# Indicador_de_8_bits.net
KiCad netlist of a schematic drawn in EasyEDA Pro
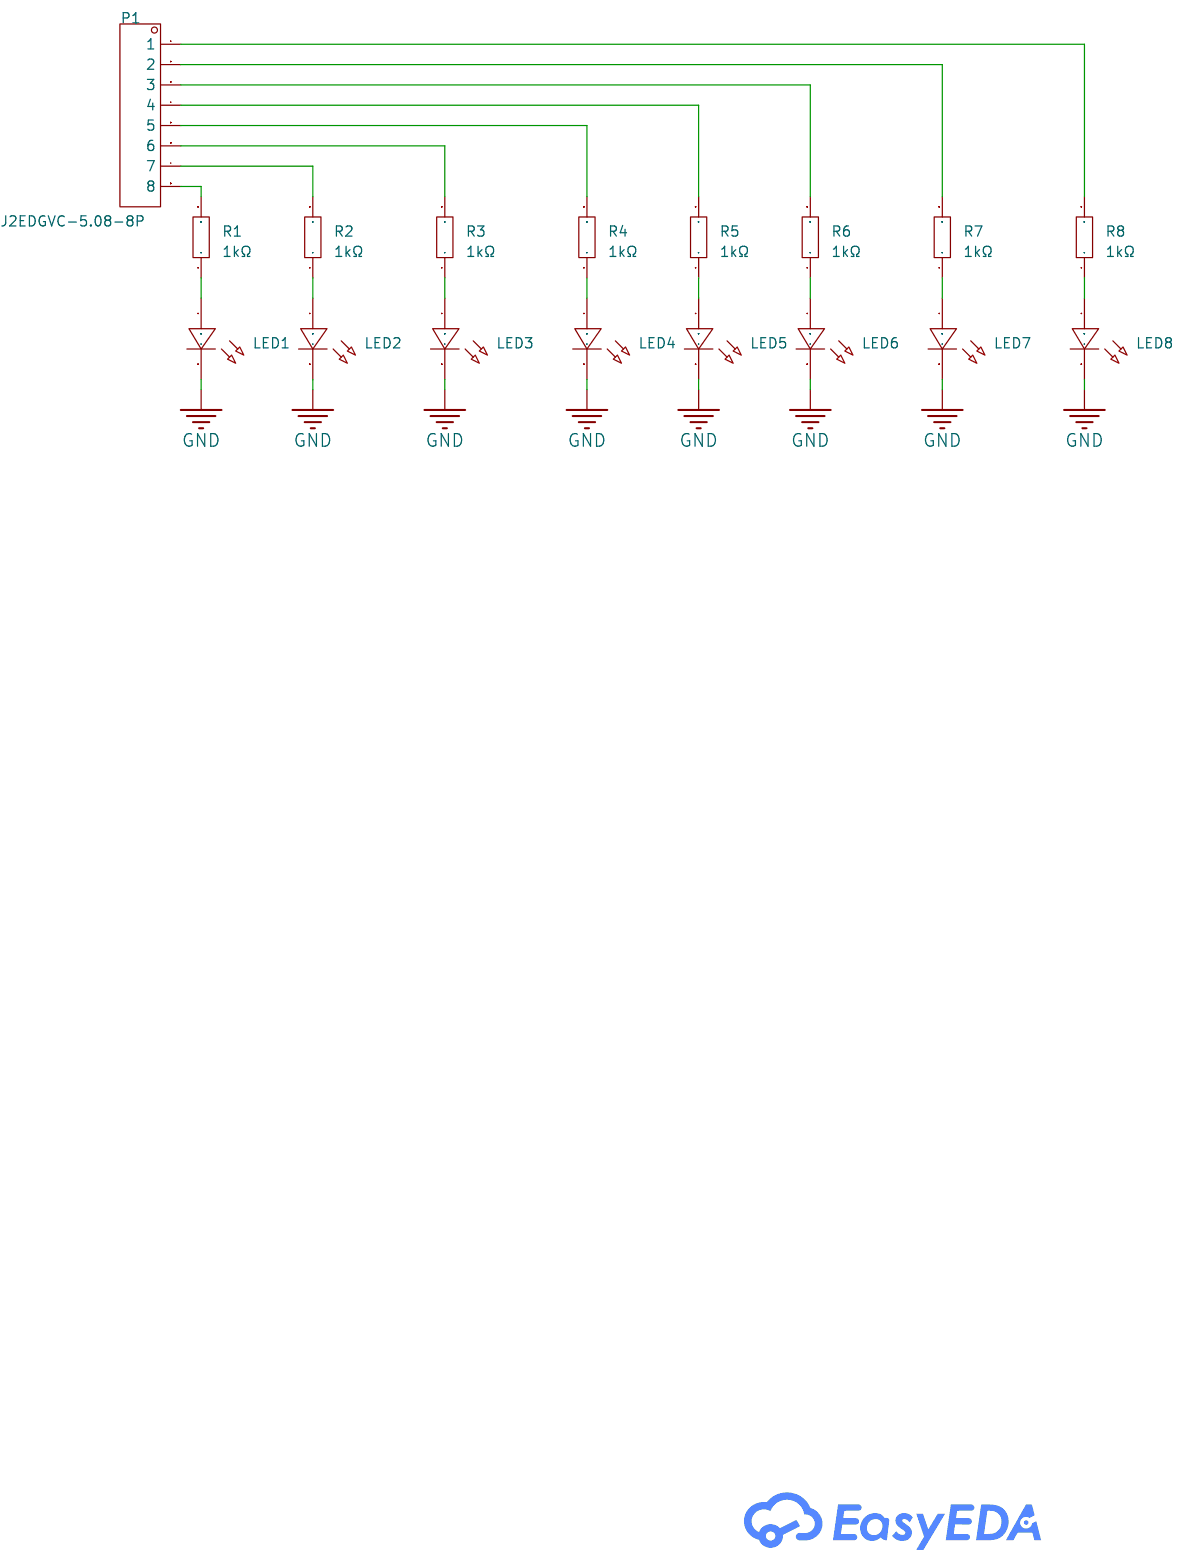
[diagram p0: schematic sheet]

(export (version "E")
  (design (tool "Eeschema 10.0.6"))
  (components
    (comp (ref "LED1")
      (value "~")
      (footprint "easyedapro:LED-TH_BD5.8-P2.54-RD")
      (libsource (lib "easyedapro") (part "LED_TH-G"))
    )
    (comp (ref "LED2")
      (value "~")
      (footprint "easyedapro:LED-TH_BD5.8-P2.54-RD")
      (libsource (lib "easyedapro") (part "LED_TH-G"))
    )
    (comp (ref "LED3")
      (value "~")
      (footprint "easyedapro:LED-TH_BD5.8-P2.54-RD")
      (libsource (lib "easyedapro") (part "LED_TH-G"))
    )
    (comp (ref "LED4")
      (value "~")
      (footprint "easyedapro:LED-TH_BD5.8-P2.54-RD")
      (libsource (lib "easyedapro") (part "LED_TH-G"))
    )
    (comp (ref "LED5")
      (value "~")
      (footprint "easyedapro:LED-TH_BD5.8-P2.54-RD")
      (libsource (lib "easyedapro") (part "LED_TH-G"))
    )
    (comp (ref "LED6")
      (value "~")
      (footprint "easyedapro:LED-TH_BD5.8-P2.54-RD")
      (libsource (lib "easyedapro") (part "LED_TH-G"))
    )
    (comp (ref "LED7")
      (value "~")
      (footprint "easyedapro:LED-TH_BD5.8-P2.54-RD")
      (libsource (lib "easyedapro") (part "LED_TH-G"))
    )
    (comp (ref "LED8")
      (value "~")
      (footprint "easyedapro:LED-TH_BD5.8-P2.54-RD")
      (libsource (lib "easyedapro") (part "LED_TH-G"))
    )
    (comp (ref "P1")
      (value "WJ2EDGVC-5.08-8P")
      (footprint "easyedapro:CONN-TH_8P_WJ2EDGVC-5.08-8P")
      (fields (field (name "Manufacturer") "KANGNEX(康奈克斯电气)"))
      (libsource (lib "easyedapro") (part "WJ2EDGVC-5.08-8P"))
    )
    (comp (ref "R1")
      (value "1kΩ")
      (footprint "easyedapro:R_AXIAL-0.4")
      (libsource (lib "easyedapro") (part "Res"))
    )
    (comp (ref "R2")
      (value "1kΩ")
      (footprint "easyedapro:R_AXIAL-0.4")
      (libsource (lib "easyedapro") (part "Res"))
    )
    (comp (ref "R3")
      (value "1kΩ")
      (footprint "easyedapro:R_AXIAL-0.4")
      (libsource (lib "easyedapro") (part "Res"))
    )
    (comp (ref "R4")
      (value "1kΩ")
      (footprint "easyedapro:R_AXIAL-0.4")
      (libsource (lib "easyedapro") (part "Res"))
    )
    (comp (ref "R5")
      (value "1kΩ")
      (footprint "easyedapro:R_AXIAL-0.4")
      (libsource (lib "easyedapro") (part "Res"))
    )
    (comp (ref "R6")
      (value "1kΩ")
      (footprint "easyedapro:R_AXIAL-0.4")
      (libsource (lib "easyedapro") (part "Res"))
    )
    (comp (ref "R7")
      (value "1kΩ")
      (footprint "easyedapro:R_AXIAL-0.4")
      (libsource (lib "easyedapro") (part "Res"))
    )
    (comp (ref "R8")
      (value "1kΩ")
      (footprint "easyedapro:R_AXIAL-0.4")
      (libsource (lib "easyedapro") (part "Res"))
    )
  )
  (nets
    (net (code "1") (name "GND") (class "Default")
      (node (ref "LED1") (pin "2") (pinfunction "A_2") (pintype "input"))
      (node (ref "LED2") (pin "2") (pinfunction "A_2") (pintype "input"))
      (node (ref "LED3") (pin "2") (pinfunction "A_2") (pintype "input"))
      (node (ref "LED4") (pin "2") (pinfunction "A_2") (pintype "input"))
      (node (ref "LED5") (pin "2") (pinfunction "A_2") (pintype "input"))
      (node (ref "LED6") (pin "2") (pinfunction "A_2") (pintype "input"))
      (node (ref "LED7") (pin "2") (pinfunction "A_2") (pintype "input"))
      (node (ref "LED8") (pin "2") (pinfunction "A_2") (pintype "input"))
    )
    (net (code "2") (name "Net-(LED1-C)") (class "Default")
      (node (ref "LED1") (pin "1") (pinfunction "C_1") (pintype "input"))
      (node (ref "R1") (pin "1") (pinfunction "1_1") (pintype "input"))
    )
    (net (code "3") (name "Net-(LED2-C)") (class "Default")
      (node (ref "LED2") (pin "1") (pinfunction "C_1") (pintype "input"))
      (node (ref "R2") (pin "1") (pinfunction "1_1") (pintype "input"))
    )
    (net (code "4") (name "Net-(LED3-C)") (class "Default")
      (node (ref "LED3") (pin "1") (pinfunction "C_1") (pintype "input"))
      (node (ref "R3") (pin "1") (pinfunction "1_1") (pintype "input"))
    )
    (net (code "5") (name "Net-(LED4-C)") (class "Default")
      (node (ref "LED4") (pin "1") (pinfunction "C_1") (pintype "input"))
      (node (ref "R4") (pin "1") (pinfunction "1_1") (pintype "input"))
    )
    (net (code "6") (name "Net-(LED5-C)") (class "Default")
      (node (ref "LED5") (pin "1") (pinfunction "C_1") (pintype "input"))
      (node (ref "R5") (pin "1") (pinfunction "1_1") (pintype "input"))
    )
    (net (code "7") (name "Net-(LED6-C)") (class "Default")
      (node (ref "LED6") (pin "1") (pinfunction "C_1") (pintype "input"))
      (node (ref "R6") (pin "1") (pinfunction "1_1") (pintype "input"))
    )
    (net (code "8") (name "Net-(LED7-C)") (class "Default")
      (node (ref "LED7") (pin "1") (pinfunction "C_1") (pintype "input"))
      (node (ref "R7") (pin "1") (pinfunction "1_1") (pintype "input"))
    )
    (net (code "9") (name "Net-(LED8-C)") (class "Default")
      (node (ref "LED8") (pin "1") (pinfunction "C_1") (pintype "input"))
      (node (ref "R8") (pin "1") (pinfunction "1_1") (pintype "input"))
    )
    (net (code "10") (name "Net-(P1-Pad1)") (class "Default")
      (node (ref "P1") (pin "1") (pinfunction "1_1") (pintype "unspecified"))
      (node (ref "R8") (pin "2") (pinfunction "2_2") (pintype "input"))
    )
    (net (code "11") (name "Net-(P1-Pad2)") (class "Default")
      (node (ref "P1") (pin "2") (pinfunction "2_2") (pintype "unspecified"))
      (node (ref "R7") (pin "2") (pinfunction "2_2") (pintype "input"))
    )
    (net (code "12") (name "Net-(P1-Pad3)") (class "Default")
      (node (ref "P1") (pin "3") (pinfunction "3_3") (pintype "unspecified"))
      (node (ref "R6") (pin "2") (pinfunction "2_2") (pintype "input"))
    )
    (net (code "13") (name "Net-(P1-Pad4)") (class "Default")
      (node (ref "P1") (pin "4") (pinfunction "4_4") (pintype "unspecified"))
      (node (ref "R5") (pin "2") (pinfunction "2_2") (pintype "input"))
    )
    (net (code "14") (name "Net-(P1-Pad5)") (class "Default")
      (node (ref "P1") (pin "5") (pinfunction "5_5") (pintype "unspecified"))
      (node (ref "R4") (pin "2") (pinfunction "2_2") (pintype "input"))
    )
    (net (code "15") (name "Net-(P1-Pad6)") (class "Default")
      (node (ref "P1") (pin "6") (pinfunction "6_6") (pintype "unspecified"))
      (node (ref "R3") (pin "2") (pinfunction "2_2") (pintype "input"))
    )
    (net (code "16") (name "Net-(P1-Pad7)") (class "Default")
      (node (ref "P1") (pin "7") (pinfunction "7_7") (pintype "unspecified"))
      (node (ref "R2") (pin "2") (pinfunction "2_2") (pintype "input"))
    )
    (net (code "17") (name "Net-(P1-Pad8)") (class "Default")
      (node (ref "P1") (pin "8") (pinfunction "8_8") (pintype "unspecified"))
      (node (ref "R1") (pin "2") (pinfunction "2_2") (pintype "input"))
    )
  )
)
